# Rotary_Angle_Card.net
KiCad netlist of a schematic drawn in EAGLE
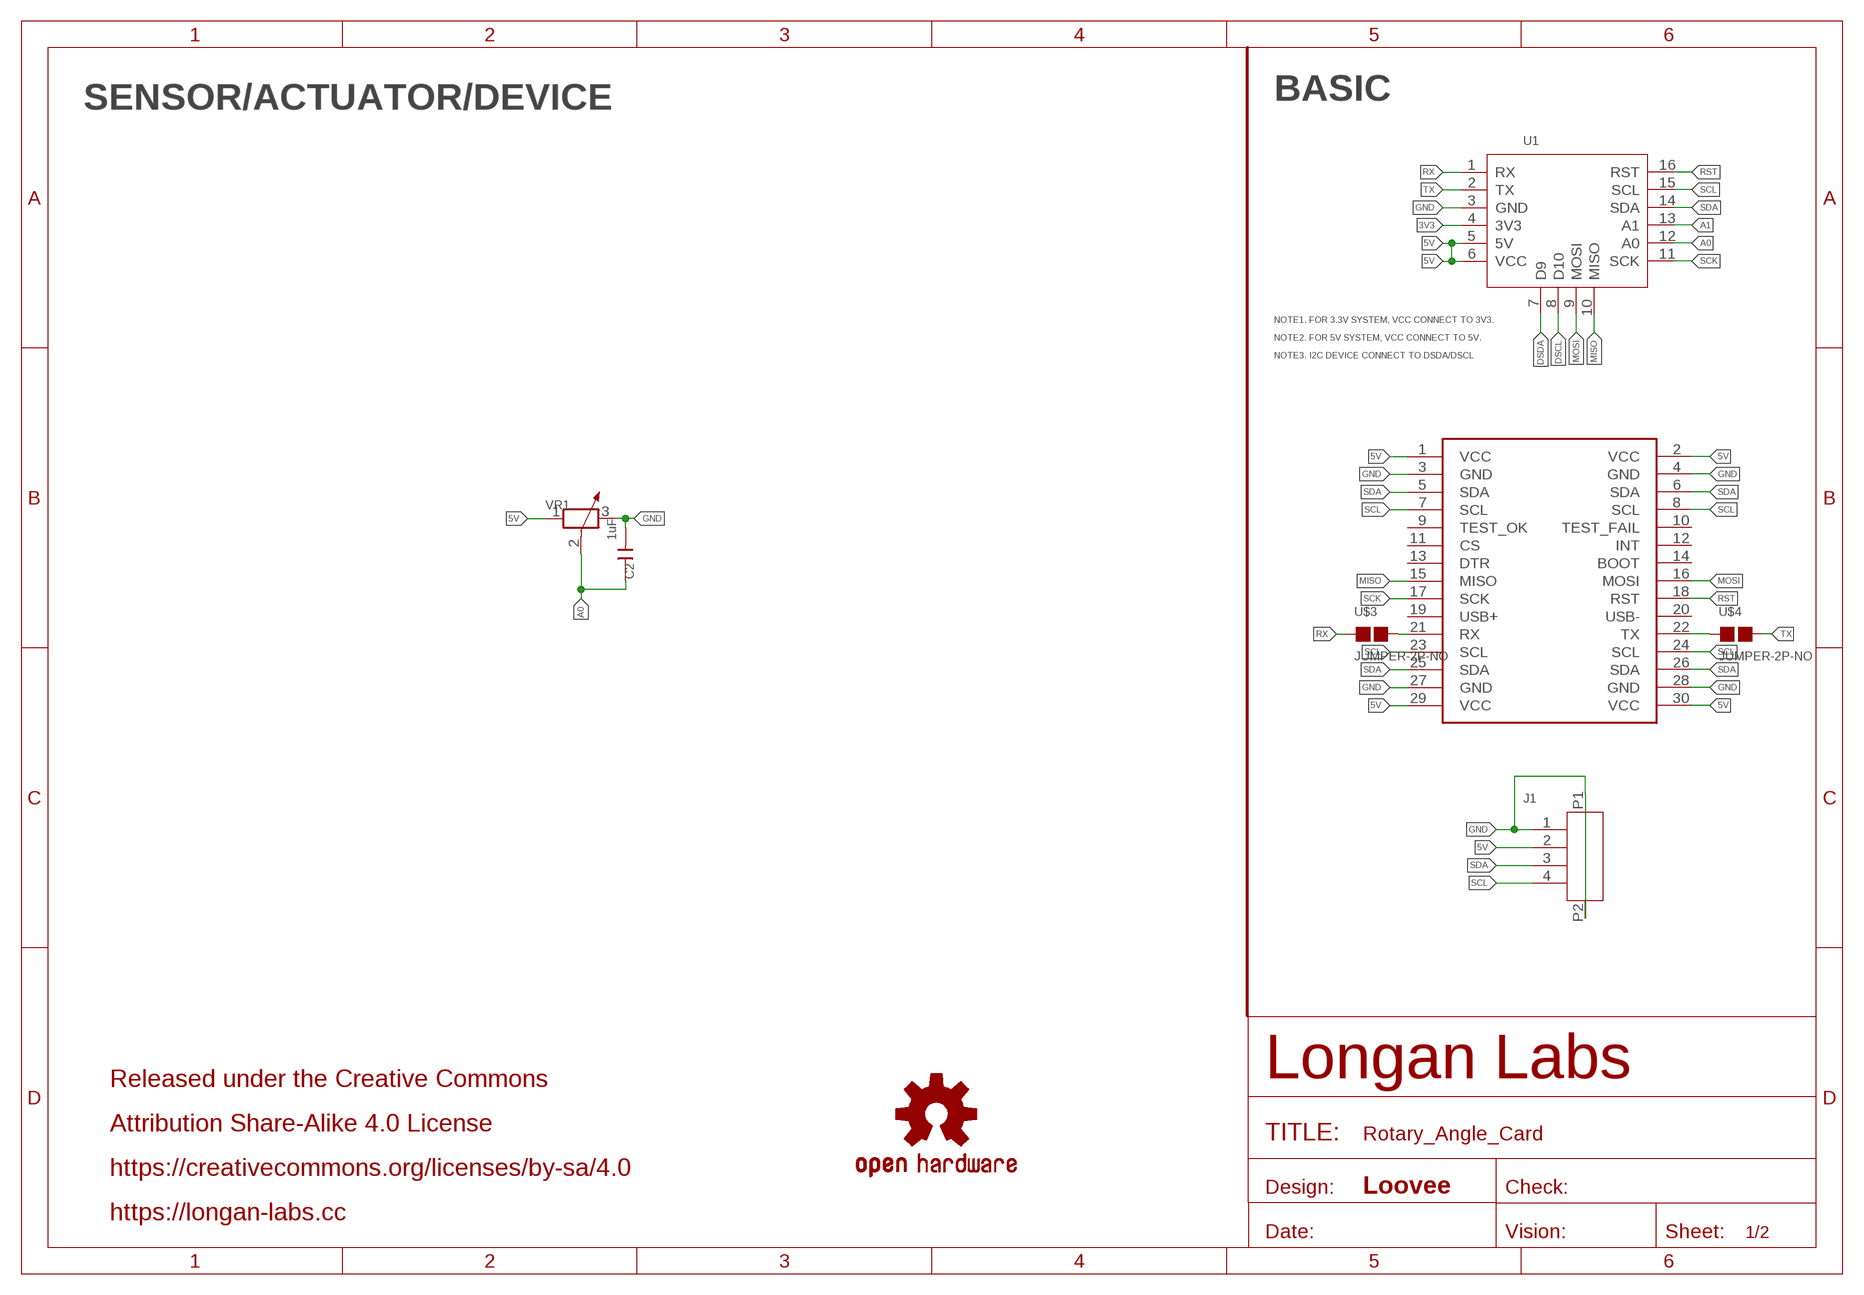
[diagram p0: schematic, sheet 1]

(export (version "E")
  (design (tool "Eeschema 10.0.6"))
  (components
    (comp (ref "C2")
      (value "1uF")
      (footprint "eagle-import:C0603")
      (libsource (lib "eagle-import") (part "CAP-0603"))
    )
    (comp (ref "J1")
      (value "HEADER-4P-1.0")
      (footprint "eagle-import:4P-1.0-90D")
      (libsource (lib "eagle-import") (part "HEADER-4P-1.0"))
    )
    (comp (ref "LOGO2")
      (value "OSHW-LOGOS")
      (footprint "eagle-import:OSHW-LOGO-S")
      (libsource (lib "eagle-import") (part "OSHW-LOGOS"))
    )
    (comp (ref "MOUDLE1")
      (value "MOUDLE-2X15P-2.54'BOARD'")
      (footprint "eagle-import:MOUDLE-2X15P-2.54")
      (libsource (lib "eagle-import") (part "MOUDLE-2X15P-2.54'BOARD'"))
    )
    (comp (ref "U$3")
      (value "JUMPER-2P-NO")
      (footprint "eagle-import:2P-SMD-NO")
      (libsource (lib "eagle-import") (part "JUMPER-2P-NO"))
    )
    (comp (ref "U$4")
      (value "JUMPER-2P-NO")
      (footprint "eagle-import:2P-SMD-NO")
      (libsource (lib "eagle-import") (part "JUMPER-2P-NO"))
    )
    (comp (ref "U1")
      (value "MOUDLE-CARDS")
      (footprint "eagle-import:16P-2.0-CARDS")
      (libsource (lib "eagle-import") (part "MOUDLE-CARDS"))
    )
    (comp (ref "VR1")
      (value "RES-ADJ")
      (footprint "eagle-import:2+3P-L11_W9.8_H12MM")
      (libsource (lib "eagle-import") (part "RES-ADJ"))
    )
  )
  (nets
    (net (code "1") (name "3V3") (class "Default")
      (node (ref "U1") (pin "4") (pinfunction "3V3_4") (pintype "bidirectional"))
    )
    (net (code "2") (name "5V") (class "Default")
      (node (ref "J1") (pin "2") (pinfunction "2_2") (pintype "bidirectional"))
      (node (ref "MOUDLE1") (pin "1") (pinfunction "VCC_1") (pintype "bidirectional"))
      (node (ref "MOUDLE1") (pin "2") (pinfunction "VCC_2") (pintype "bidirectional"))
      (node (ref "MOUDLE1") (pin "29") (pinfunction "VCC_29") (pintype "bidirectional"))
      (node (ref "MOUDLE1") (pin "30") (pinfunction "VCC_30") (pintype "bidirectional"))
      (node (ref "U1") (pin "5") (pinfunction "5V_5") (pintype "bidirectional"))
      (node (ref "U1") (pin "6") (pinfunction "VCC_6") (pintype "bidirectional"))
      (node (ref "VR1") (pin "1") (pinfunction "1_1") (pintype "passive"))
    )
    (net (code "3") (name "A0") (class "Default")
      (node (ref "C2") (pin "1") (pinfunction "1_1") (pintype "passive"))
      (node (ref "U1") (pin "12") (pinfunction "A0_12") (pintype "bidirectional"))
      (node (ref "VR1") (pin "2") (pinfunction "3_2") (pintype "passive"))
    )
    (net (code "4") (name "A1") (class "Default")
      (node (ref "U1") (pin "13") (pinfunction "A1_13") (pintype "bidirectional"))
    )
    (net (code "5") (name "DSCL") (class "Default")
      (node (ref "U1") (pin "8") (pinfunction "D10_8") (pintype "bidirectional"))
    )
    (net (code "6") (name "DSDA") (class "Default")
      (node (ref "U1") (pin "7") (pinfunction "D9_7") (pintype "bidirectional"))
    )
    (net (code "7") (name "GND") (class "Default")
      (node (ref "C2") (pin "2") (pinfunction "2_2") (pintype "passive"))
      (node (ref "J1") (pin "1") (pinfunction "1_1") (pintype "bidirectional"))
      (node (ref "J1") (pin "P1") (pinfunction "P1_P1") (pintype "bidirectional"))
      (node (ref "J1") (pin "P2") (pinfunction "P2_P2") (pintype "bidirectional"))
      (node (ref "MOUDLE1") (pin "27") (pinfunction "GND_27") (pintype "bidirectional"))
      (node (ref "MOUDLE1") (pin "28") (pinfunction "GND_28") (pintype "bidirectional"))
      (node (ref "MOUDLE1") (pin "3") (pinfunction "GND_3") (pintype "bidirectional"))
      (node (ref "MOUDLE1") (pin "4") (pinfunction "GND_4") (pintype "bidirectional"))
      (node (ref "U1") (pin "3") (pinfunction "GND_3") (pintype "bidirectional"))
      (node (ref "VR1") (pin "3") (pinfunction "2_3") (pintype "passive"))
    )
    (net (code "8") (name "MISO") (class "Default")
      (node (ref "MOUDLE1") (pin "15") (pinfunction "MISO_15") (pintype "bidirectional"))
      (node (ref "U1") (pin "10") (pinfunction "MISO_10") (pintype "bidirectional"))
    )
    (net (code "9") (name "MOSI") (class "Default")
      (node (ref "MOUDLE1") (pin "16") (pinfunction "MOSI_16") (pintype "bidirectional"))
      (node (ref "U1") (pin "9") (pinfunction "MOSI_9") (pintype "bidirectional"))
    )
    (net (code "10") (name "Net-(MOUDLE1-RX)") (class "Default")
      (node (ref "MOUDLE1") (pin "21") (pinfunction "RX_21") (pintype "bidirectional"))
      (node (ref "U$3") (pin "2") (pinfunction "2_2") (pintype "bidirectional"))
    )
    (net (code "11") (name "Net-(MOUDLE1-TX)") (class "Default")
      (node (ref "MOUDLE1") (pin "22") (pinfunction "TX_22") (pintype "bidirectional"))
      (node (ref "U$4") (pin "1") (pinfunction "1_1") (pintype "bidirectional"))
    )
    (net (code "12") (name "RST") (class "Default")
      (node (ref "MOUDLE1") (pin "18") (pinfunction "RST_18") (pintype "bidirectional"))
      (node (ref "U1") (pin "16") (pinfunction "RST_16") (pintype "bidirectional"))
    )
    (net (code "13") (name "RX") (class "Default")
      (node (ref "U$3") (pin "1") (pinfunction "1_1") (pintype "bidirectional"))
      (node (ref "U1") (pin "1") (pinfunction "RX_1") (pintype "bidirectional"))
    )
    (net (code "14") (name "SCK") (class "Default")
      (node (ref "MOUDLE1") (pin "17") (pinfunction "SCK_17") (pintype "bidirectional"))
      (node (ref "U1") (pin "11") (pinfunction "SCK_11") (pintype "bidirectional"))
    )
    (net (code "15") (name "SCL") (class "Default")
      (node (ref "J1") (pin "4") (pinfunction "4_4") (pintype "bidirectional"))
      (node (ref "MOUDLE1") (pin "23") (pinfunction "SCL_23") (pintype "bidirectional"))
      (node (ref "MOUDLE1") (pin "24") (pinfunction "SCL_24") (pintype "bidirectional"))
      (node (ref "MOUDLE1") (pin "7") (pinfunction "SCL_7") (pintype "bidirectional"))
      (node (ref "MOUDLE1") (pin "8") (pinfunction "SCL_8") (pintype "bidirectional"))
      (node (ref "U1") (pin "15") (pinfunction "SCL_15") (pintype "bidirectional"))
    )
    (net (code "16") (name "SDA") (class "Default")
      (node (ref "J1") (pin "3") (pinfunction "3_3") (pintype "bidirectional"))
      (node (ref "MOUDLE1") (pin "25") (pinfunction "SDA_25") (pintype "bidirectional"))
      (node (ref "MOUDLE1") (pin "26") (pinfunction "SDA_26") (pintype "bidirectional"))
      (node (ref "MOUDLE1") (pin "5") (pinfunction "SDA_5") (pintype "bidirectional"))
      (node (ref "MOUDLE1") (pin "6") (pinfunction "SDA_6") (pintype "bidirectional"))
      (node (ref "U1") (pin "14") (pinfunction "SDA_14") (pintype "bidirectional"))
    )
    (net (code "17") (name "TX") (class "Default")
      (node (ref "U$4") (pin "2") (pinfunction "2_2") (pintype "bidirectional"))
      (node (ref "U1") (pin "2") (pinfunction "TX_2") (pintype "bidirectional"))
    )
    (net (code "18") (name "unconnected-(MOUDLE1-BOOT-Pad14)") (class "Default")
      (node (ref "MOUDLE1") (pin "14") (pinfunction "BOOT_14") (pintype "bidirectional"))
    )
    (net (code "19") (name "unconnected-(MOUDLE1-CS-Pad11)") (class "Default")
      (node (ref "MOUDLE1") (pin "11") (pinfunction "CS_11") (pintype "bidirectional"))
    )
    (net (code "20") (name "unconnected-(MOUDLE1-DTR-Pad13)") (class "Default")
      (node (ref "MOUDLE1") (pin "13") (pinfunction "DTR_13") (pintype "bidirectional"))
    )
    (net (code "21") (name "unconnected-(MOUDLE1-INT-Pad12)") (class "Default")
      (node (ref "MOUDLE1") (pin "12") (pinfunction "INT_12") (pintype "bidirectional"))
    )
    (net (code "22") (name "unconnected-(MOUDLE1-TEST_FAIL-Pad10)") (class "Default")
      (node (ref "MOUDLE1") (pin "10") (pinfunction "TEST_FAIL_10") (pintype "bidirectional"))
    )
    (net (code "23") (name "unconnected-(MOUDLE1-TEST_OK-Pad9)") (class "Default")
      (node (ref "MOUDLE1") (pin "9") (pinfunction "TEST_OK_9") (pintype "bidirectional"))
    )
    (net (code "24") (name "unconnected-(MOUDLE1-USB+-Pad19)") (class "Default")
      (node (ref "MOUDLE1") (pin "19") (pinfunction "USB+_19") (pintype "bidirectional"))
    )
    (net (code "25") (name "unconnected-(MOUDLE1-USB--Pad20)") (class "Default")
      (node (ref "MOUDLE1") (pin "20") (pinfunction "USB-_20") (pintype "bidirectional"))
    )
  )
)
